# 08_-_LoRa_RAK3172.net
KiCad netlist of a schematic drawn in Altium Designer
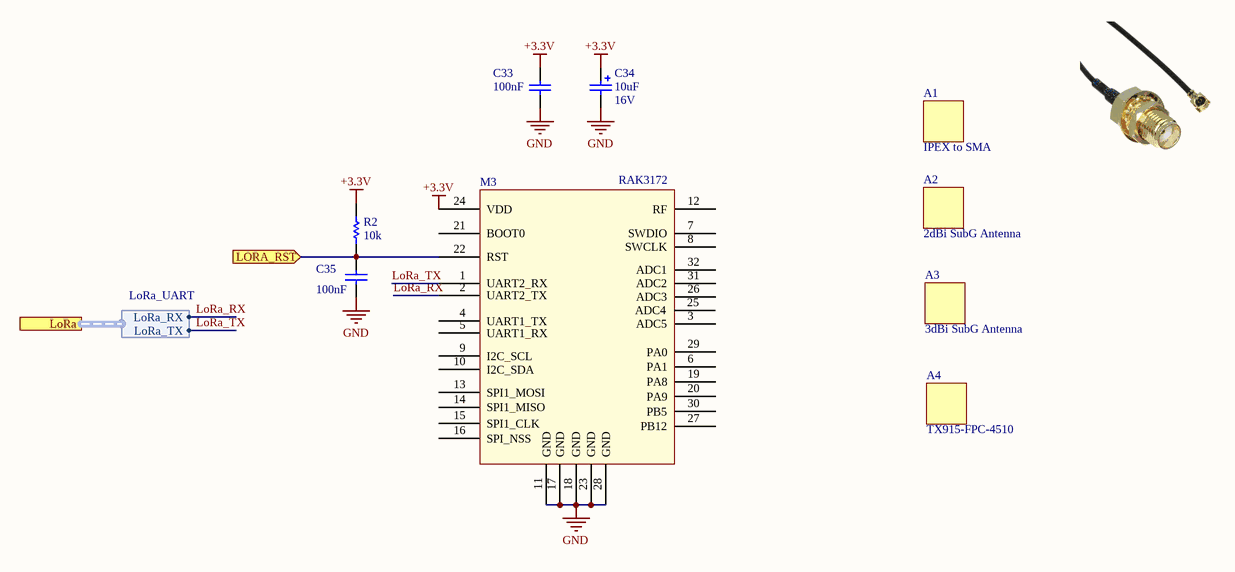
[diagram p0: [08] - LoRa_RAK3172.SchDoc]

(export (version "E")
  (design (tool "Eeschema 10.0.6"))
  (components
    (comp (ref "A1")
      (value "IPEX to SMA")
      (description "IPEX to SMA adapter cable")
      (libsource (lib "BaseNode v1.2") (part "Mechanical_component"))
    )
    (comp (ref "A2")
      (value "2dBi SubG Antenna")
      (libsource (lib "BaseNode v1.2") (part "Mechanical_component"))
    )
    (comp (ref "A3")
      (value "3dBi SubG Antenna")
      (libsource (lib "BaseNode v1.2") (part "Mechanical_component"))
    )
    (comp (ref "A4")
      (value "TX915-FPC-4510")
      (description "TX915-FPC-4510 868~930MHz adhesive antenna")
      (libsource (lib "BaseNode v1.2") (part "Mechanical_component"))
    )
    (comp (ref "C33")
      (value "Capacitor")
      (footprint "Blue Tractor-2021:0603_C")
      (description "Cap Ceramic 0.1uF 50VDC X7R 10% SMD 0603 Paper T/R")
      (fields
        (field (name "MANUFACTURER") "Samsung")
        (field (name "MANUFACTURER PART NUMBER") "CL10B104KB8NNNC")
        (field (name "CAPACITANCE") "100nF")
      )
      (libsource (lib "Altium_Library") (part "Capacitor"))
    )
    (comp (ref "C34")
      (value "Capacitor Polarized")
      (footprint "Tantalum 3216 A")
      (description "CAP TANT 10UF 10% 16V 1206")
      (fields
        (field (name "MANUFACTURER") "Vishay Sprague")
        (field (name "MANUFACTURER PART NUMBER") "293D106X9016A2TE3")
        (field (name "CAPACITANCE") "10uF")
        (field (name "VOLTAGE RATING") "16V")
      )
      (libsource (lib "Altium_Library") (part "Capacitor Polarized"))
    )
    (comp (ref "C35")
      (value "Capacitor")
      (footprint "Blue Tractor-2021:0603_C")
      (description "Cap Ceramic 0.1uF 50VDC X7R 10% SMD 0603 Paper T/R")
      (fields
        (field (name "MANUFACTURER") "Samsung")
        (field (name "MANUFACTURER PART NUMBER") "CL10B104KB8NNNC")
        (field (name "CAPACITANCE") "100nF")
      )
      (libsource (lib "Altium_Library") (part "Capacitor"))
    )
    (comp (ref "M3")
      (value "RAK3172")
      (footprint "Blue Tractor-2021:RAK3172")
      (libsource (lib "Blue Tractor-2021") (part "LoRa RAK3172"))
    )
    (comp (ref "R2")
      (value "Res1")
      (footprint "Res-0603")
      (description "Chip Resistor")
      (fields
        (field (name "MANUFACTURER") "Panasonic")
        (field (name "MANUFACTURER PART NUMBER") "ERJ-3GEYJ103V")
        (field (name "RESISTANCE") "10k")
      )
      (libsource (lib "Altium_Library") (part "Res1"))
    )
  )
  (nets
    (net (code "2") (name "+3.3V") (class "Default")
      (node (ref "C33") (pin "2") (pinfunction "2_2") (pintype "passive"))
      (node (ref "C34") (pin "1") (pinfunction "1_1") (pintype "passive"))
      (node (ref "M3") (pin "24") (pinfunction "VDD_24") (pintype "power_in"))
      (node (ref "R2") (pin "2") (pinfunction "2_2") (pintype "passive"))
    )
    (net (code "3") (name "/LORA_RST") (class "Default")
      (node (ref "C35") (pin "2") (pinfunction "2_2") (pintype "passive"))
      (node (ref "M3") (pin "22") (pinfunction "RST_22") (pintype "passive"))
      (node (ref "R2") (pin "1") (pinfunction "1_1") (pintype "passive"))
    )
    (net (code "4") (name "/LoRa_RX") (class "Default")
      (node (ref "M3") (pin "2") (pinfunction "UART2_TX_2") (pintype "passive"))
    )
    (net (code "5") (name "/LoRa_TX") (class "Default")
      (node (ref "M3") (pin "1") (pinfunction "UART2_RX_1") (pintype "passive"))
    )
    (net (code "7") (name "GND") (class "Default")
      (node (ref "C33") (pin "1") (pinfunction "1_1") (pintype "passive"))
      (node (ref "C34") (pin "2") (pinfunction "2_2") (pintype "passive"))
      (node (ref "C35") (pin "1") (pinfunction "1_1") (pintype "passive"))
      (node (ref "M3") (pin "11") (pinfunction "GND_11") (pintype "passive"))
      (node (ref "M3") (pin "17") (pinfunction "GND_17") (pintype "passive"))
      (node (ref "M3") (pin "18") (pinfunction "GND_18") (pintype "passive"))
      (node (ref "M3") (pin "23") (pinfunction "GND_23") (pintype "passive"))
      (node (ref "M3") (pin "28") (pinfunction "GND_28") (pintype "passive"))
    )
    (net (code "8") (name "unconnected-(M3-ADC1-Pad32)") (class "Default")
      (node (ref "M3") (pin "32") (pinfunction "ADC1_32") (pintype "power_in"))
    )
    (net (code "9") (name "unconnected-(M3-ADC2-Pad31)") (class "Default")
      (node (ref "M3") (pin "31") (pinfunction "ADC2_31") (pintype "power_in"))
    )
    (net (code "10") (name "unconnected-(M3-ADC3-Pad26)") (class "Default")
      (node (ref "M3") (pin "26") (pinfunction "ADC3_26") (pintype "power_in"))
    )
    (net (code "11") (name "unconnected-(M3-ADC4-Pad25)") (class "Default")
      (node (ref "M3") (pin "25") (pinfunction "ADC4_25") (pintype "power_in"))
    )
    (net (code "12") (name "unconnected-(M3-ADC5-Pad3)") (class "Default")
      (node (ref "M3") (pin "3") (pinfunction "ADC5_3") (pintype "power_in"))
    )
    (net (code "13") (name "unconnected-(M3-BOOT0-Pad21)") (class "Default")
      (node (ref "M3") (pin "21") (pinfunction "BOOT0_21") (pintype "passive"))
    )
    (net (code "14") (name "unconnected-(M3-I2C_SCL-Pad9)") (class "Default")
      (node (ref "M3") (pin "9") (pinfunction "I2C_SCL_9") (pintype "passive"))
    )
    (net (code "15") (name "unconnected-(M3-I2C_SDA-Pad10)") (class "Default")
      (node (ref "M3") (pin "10") (pinfunction "I2C_SDA_10") (pintype "passive"))
    )
    (net (code "16") (name "unconnected-(M3-PA0-Pad29)") (class "Default")
      (node (ref "M3") (pin "29") (pinfunction "PA0_29") (pintype "power_in"))
    )
    (net (code "17") (name "unconnected-(M3-PA1-Pad6)") (class "Default")
      (node (ref "M3") (pin "6") (pinfunction "PA1_6") (pintype "power_in"))
    )
    (net (code "18") (name "unconnected-(M3-PA8-Pad19)") (class "Default")
      (node (ref "M3") (pin "19") (pinfunction "PA8_19") (pintype "power_in"))
    )
    (net (code "19") (name "unconnected-(M3-PA9-Pad20)") (class "Default")
      (node (ref "M3") (pin "20") (pinfunction "PA9_20") (pintype "power_in"))
    )
    (net (code "20") (name "unconnected-(M3-PB5-Pad30)") (class "Default")
      (node (ref "M3") (pin "30") (pinfunction "PB5_30") (pintype "power_in"))
    )
    (net (code "21") (name "unconnected-(M3-PB12-Pad27)") (class "Default")
      (node (ref "M3") (pin "27") (pinfunction "PB12_27") (pintype "power_in"))
    )
    (net (code "22") (name "unconnected-(M3-RF-Pad12)") (class "Default")
      (node (ref "M3") (pin "12") (pinfunction "RF_12") (pintype "power_in"))
    )
    (net (code "23") (name "unconnected-(M3-SPI1_CLK-Pad15)") (class "Default")
      (node (ref "M3") (pin "15") (pinfunction "SPI1_CLK_15") (pintype "passive"))
    )
    (net (code "24") (name "unconnected-(M3-SPI1_MISO-Pad14)") (class "Default")
      (node (ref "M3") (pin "14") (pinfunction "SPI1_MISO_14") (pintype "passive"))
    )
    (net (code "25") (name "unconnected-(M3-SPI1_MOSI-Pad13)") (class "Default")
      (node (ref "M3") (pin "13") (pinfunction "SPI1_MOSI_13") (pintype "passive"))
    )
    (net (code "26") (name "unconnected-(M3-SPI_NSS-Pad16)") (class "Default")
      (node (ref "M3") (pin "16") (pinfunction "SPI_NSS_16") (pintype "passive"))
    )
    (net (code "27") (name "unconnected-(M3-SWCLK-Pad8)") (class "Default")
      (node (ref "M3") (pin "8") (pinfunction "SWCLK_8") (pintype "power_in"))
    )
    (net (code "28") (name "unconnected-(M3-SWDIO-Pad7)") (class "Default")
      (node (ref "M3") (pin "7") (pinfunction "SWDIO_7") (pintype "power_in"))
    )
    (net (code "29") (name "unconnected-(M3-UART1_RX-Pad5)") (class "Default")
      (node (ref "M3") (pin "5") (pinfunction "UART1_RX_5") (pintype "passive"))
    )
    (net (code "30") (name "unconnected-(M3-UART1_TX-Pad4)") (class "Default")
      (node (ref "M3") (pin "4") (pinfunction "UART1_TX_4") (pintype "passive"))
    )
  )
)
